# eBox_3G_SIM.net
KiCad netlist of a schematic drawn in Altium Designer
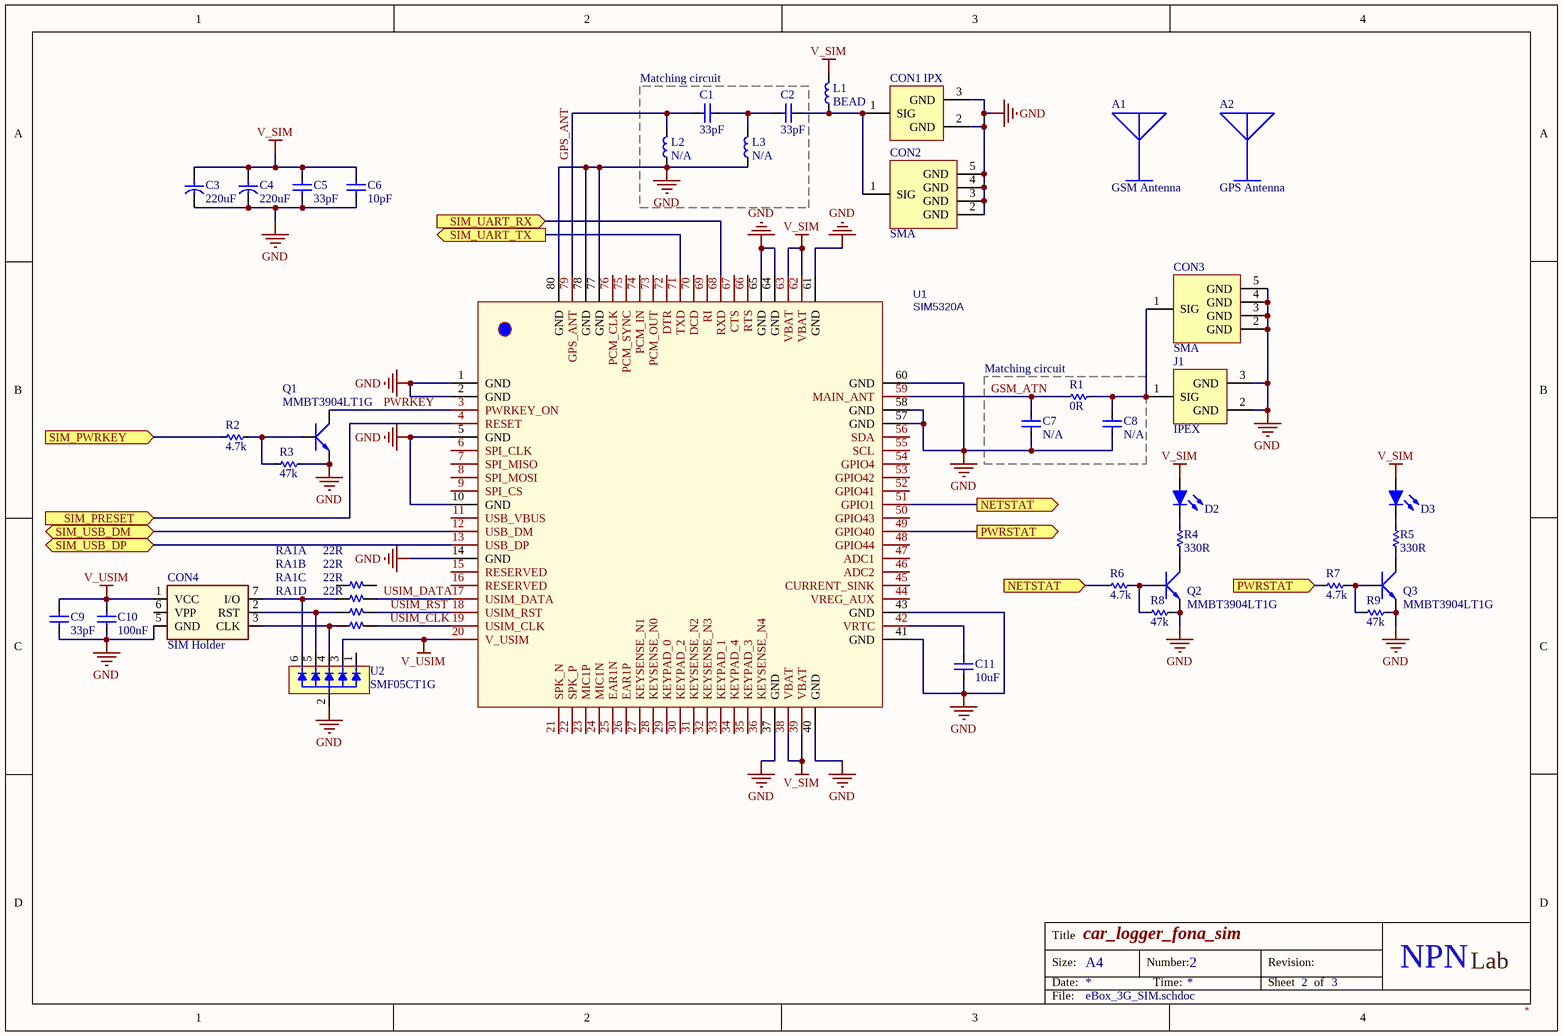
[diagram p0: eBox_3G_SIM.schdoc]

(export (version "E")
  (design (tool "Eeschema 10.0.6"))
  (components
    (comp (ref "A1")
      (value "GSM Antenna")
      (footprint "Antenna")
      (description "Antenna")
      (libsource (lib "car_logger_libs") (part "Antenna"))
    )
    (comp (ref "A2")
      (value "GPS Antenna")
      (footprint "Antenna")
      (description "Antenna")
      (libsource (lib "car_logger_libs") (part "Antenna"))
    )
    (comp (ref "C1")
      (value "33pF")
      (footprint "CC 0603")
      (description "CAP CER 33PF 100V C0G/NP0 0603")
      (fields
        (field (name "MANUFACTURER") "Murata Electronics")
        (field (name "MANUFACTURER PART NUMBER") "GCM1885C2A330JA16D")
      )
      (libsource (lib "car_logger_libs") (part "Capacitor NP"))
    )
    (comp (ref "C2")
      (value "33pF")
      (footprint "CC 0603")
      (description "CAP CER 33PF 100V C0G/NP0 0603")
      (fields
        (field (name "MANUFACTURER") "Murata Electronics")
        (field (name "MANUFACTURER PART NUMBER") "GCM1885C2A330JA16D")
      )
      (libsource (lib "car_logger_libs") (part "Capacitor NP"))
    )
    (comp (ref "C3")
      (value "220uF")
      (footprint "C SMD ALU (D8)")
      (description "CAP TANT POLY 100UF 6.3V 1210")
      (fields
        (field (name "MANUFACTURER") "AVX Corporation")
        (field (name "MANUFACTURER PART NUMBER") "TCJB107M006R0055")
      )
      (libsource (lib "ChipFC_Lib") (part "Capacitor"))
    )
    (comp (ref "C4")
      (value "220uF")
      (footprint "C SMD ALU (D8)")
      (description "CAP TANT POLY 100UF 6.3V 1210")
      (fields
        (field (name "MANUFACTURER") "AVX Corporation")
        (field (name "MANUFACTURER PART NUMBER") "TCJB107M006R0055")
      )
      (libsource (lib "ChipFC_Lib") (part "Capacitor"))
    )
    (comp (ref "C5")
      (value "33pF")
      (footprint "CC 0603")
      (description "CAP CER 33PF 100V C0G/NP0 0603")
      (fields
        (field (name "MANUFACTURER") "Murata Electronics")
        (field (name "MANUFACTURER PART NUMBER") "GCM1885C2A330JA16D")
      )
      (libsource (lib "car_logger_libs") (part "Capacitor NP"))
    )
    (comp (ref "C6")
      (value "10pF")
      (footprint "CC 0603")
      (description "CAP CER 10PF 100V C0G/NP0 0603")
      (fields
        (field (name "MANUFACTURER") "Murata Electronics")
        (field (name "MANUFACTURER PART NUMBER") "GCM1885C2A100JA16D")
      )
      (libsource (lib "car_logger_libs") (part "Capacitor NP"))
    )
    (comp (ref "C7")
      (value "N/A")
      (footprint "CC 0603")
      (description "CAP N/A")
      (libsource (lib "car_logger_libs") (part "Capacitor NP"))
    )
    (comp (ref "C8")
      (value "N/A")
      (footprint "CC 0603")
      (description "CAP N/A")
      (libsource (lib "car_logger_libs") (part "Capacitor NP"))
    )
    (comp (ref "C9")
      (value "33pF")
      (footprint "CC 0603")
      (description "CAP CER 33PF 100V C0G/NP0 0603")
      (fields
        (field (name "MANUFACTURER") "Murata Electronics")
        (field (name "MANUFACTURER PART NUMBER") "GCM1885C2A330JA16D")
      )
      (libsource (lib "car_logger_libs") (part "Capacitor NP"))
    )
    (comp (ref "C10")
      (value "100nF")
      (footprint "CC 0603")
      (description "CAP CER 0.1UF 16V X7R 0603")
      (fields
        (field (name "MANUFACTURER") "Murata Electronics")
        (field (name "MANUFACTURER PART NUMBER") "GCJ188R71C104KA01D")
      )
      (libsource (lib "car_logger_libs") (part "Capacitor NP"))
    )
    (comp (ref "C11")
      (value "10uF")
      (footprint "CC 0805")
      (description "CAP CER 10UF 10V X5R 0603")
      (fields
        (field (name "MANUFACTURER") "Murata Electronics")
        (field (name "MANUFACTURER PART NUMBER") "GRM188R61A106KE69D")
      )
      (libsource (lib "car_logger_libs") (part "Capacitor NP"))
    )
    (comp (ref "CON1")
      (value "IPX")
      (footprint "CONN/IPX/SMD")
      (libsource (lib "chipfc_altium_libs") (part "CON IPX"))
    )
    (comp (ref "CON2")
      (value "SMA")
      (footprint "CONN/SMA/RA")
      (description "SMA connectors")
      (libsource (lib "chipfc_altium_libs") (part "CON SMA"))
    )
    (comp (ref "CON3")
      (value "SMA")
      (footprint "CONN/SMA/RA")
      (description "SMA connectors")
      (libsource (lib "chipfc_altium_libs") (part "CON SMA"))
    )
    (comp (ref "CON4")
      (value "SIM Holder")
      (footprint "CON SIM Holder C707")
      (description "SIM Card holder, 6 pins")
      (libsource (lib "chipfc_altium_libs") (part "SIM holder 6 pin"))
    )
    (comp (ref "D2")
      (value "LED GREEN")
      (footprint "Led 0603 - green")
      (description "LED GREEN DIFFUSED 0603 SMD")
      (fields
        (field (name "MANUFACTURER") "Rohm Semiconductor")
        (field (name "MANUFACTURER PART NUMBER") "SML-D12P8WT86")
      )
      (libsource (lib "ChipFC_Lib") (part "Led"))
    )
    (comp (ref "D3")
      (value "LED RED")
      (footprint "Led 0603 - red")
      (description "LED RED DIFFUSED 0603 SMD")
      (fields
        (field (name "MANUFACTURER") "Rohm Semiconductor")
        (field (name "MANUFACTURER PART NUMBER") "SML-D12U8WT86")
      )
      (libsource (lib "ChipFC_Lib") (part "Led"))
    )
    (comp (ref "J1")
      (value "IPEX")
      (footprint "CONN/IPX/SMD")
      (description "CONN UMC RCPT STR 50 OHM SMD")
      (fields
        (field (name "MANUFACTURER") "Taoglas Limited")
        (field (name "MANUFACTURER PART NUMBER") "RECE.20279.001E.01")
      )
      (libsource (lib "ChipFC_Lib") (part "CON IPX"))
    )
    (comp (ref "L1")
      (value "BEAD")
      (footprint "LL 0603")
      (description "FERRITE BEAD 30 OHM 0603 1LN")
      (fields
        (field (name "MANUFACTURER") "Vishay Dale")
        (field (name "MANUFACTURER PART NUMBER") "ILBB0603ER300V")
      )
      (libsource (lib "car_logger_libs") (part "Inductor"))
    )
    (comp (ref "L2")
      (value "N/A")
      (footprint "LL 0603")
      (description "IND N/A")
      (libsource (lib "car_logger_libs") (part "Inductor"))
    )
    (comp (ref "L3")
      (value "N/A")
      (footprint "LL 0603")
      (description "IND N/A")
      (libsource (lib "car_logger_libs") (part "Inductor"))
    )
    (comp (ref "Q1")
      (value "MMBT3904LT1G")
      (footprint "SOT-23")
      (description "TRANS NPN 40V 0.2A SOT23")
      (fields (field (name "MANUFACTURER") "ON Semiconductor"))
      (libsource (lib "car_logger_libs") (part "MMBT3904LT1G"))
    )
    (comp (ref "Q2")
      (value "MMBT3904LT1G")
      (footprint "SOT-23")
      (description "TRANS NPN 40V 0.2A SOT23")
      (fields (field (name "MANUFACTURER") "ON Semiconductor"))
      (libsource (lib "car_logger_libs") (part "MMBT3904LT1G"))
    )
    (comp (ref "Q3")
      (value "MMBT3904LT1G")
      (footprint "SOT-23")
      (description "TRANS NPN 40V 0.2A SOT23")
      (fields (field (name "MANUFACTURER") "ON Semiconductor"))
      (libsource (lib "car_logger_libs") (part "MMBT3904LT1G"))
    )
    (comp (ref "R1")
      (value "0R")
      (footprint "RR 0603")
      (description "RES SMD 0 OHM JUMPER 1/10W 0603")
      (fields
        (field (name "MANUFACTURER") "Panasonic Industrial Devices")
        (field (name "MANUFACTURER PART NUMBER") "ERJ-3GEY0R00V")
      )
      (libsource (lib "car_logger_libs") (part "Resistors"))
    )
    (comp (ref "R2")
      (value "4.7k")
      (footprint "RR 0603")
      (description "RES SMD 4.7K OHM 1% 1/10W 0603")
      (fields
        (field (name "MANUFACTURER") "Panasonic Industrial Devices")
        (field (name "MANUFACTURER PART NUMBER") "ERJ-3EKF4701V")
      )
      (libsource (lib "car_logger_libs") (part "Resistors"))
    )
    (comp (ref "R3")
      (value "47k")
      (footprint "RR 0603")
      (description "RES SMD 47K OHM 5% 1/10W 0603")
      (fields
        (field (name "MANUFACTURER") "Panasonic Industrial Devices")
        (field (name "MANUFACTURER PART NUMBER") "ERJ-3GEYJ473V")
      )
      (libsource (lib "car_logger_libs") (part "Resistors"))
    )
    (comp (ref "R4")
      (value "330R")
      (footprint "RR 0603")
      (description "RES SMD 330 OHM 5% 1/10W 0603")
      (fields
        (field (name "MANUFACTURER") "Panasonic Industrial Devices")
        (field (name "MANUFACTURER PART NUMBER") "ERJ-3GEYJ331V")
      )
      (libsource (lib "car_logger_libs") (part "Resistors"))
    )
    (comp (ref "R5")
      (value "330R")
      (footprint "RR 0603")
      (description "RES SMD 330 OHM 5% 1/10W 0603")
      (fields
        (field (name "MANUFACTURER") "Panasonic Industrial Devices")
        (field (name "MANUFACTURER PART NUMBER") "ERJ-3GEYJ331V")
      )
      (libsource (lib "car_logger_libs") (part "Resistors"))
    )
    (comp (ref "R6")
      (value "4.7k")
      (footprint "RR 0603")
      (description "RES SMD 4.7K OHM 1% 1/10W 0603")
      (fields
        (field (name "MANUFACTURER") "Panasonic Industrial Devices")
        (field (name "MANUFACTURER PART NUMBER") "ERJ-3EKF4701V")
      )
      (libsource (lib "car_logger_libs") (part "Resistors"))
    )
    (comp (ref "R7")
      (value "4.7k")
      (footprint "RR 0603")
      (description "RES SMD 4.7K OHM 1% 1/10W 0603")
      (fields
        (field (name "MANUFACTURER") "Panasonic Industrial Devices")
        (field (name "MANUFACTURER PART NUMBER") "ERJ-3EKF4701V")
      )
      (libsource (lib "car_logger_libs") (part "Resistors"))
    )
    (comp (ref "R8")
      (value "47k")
      (footprint "RR 0603")
      (description "RES SMD 47K OHM 5% 1/10W 0603")
      (fields
        (field (name "MANUFACTURER") "Panasonic Industrial Devices")
        (field (name "MANUFACTURER PART NUMBER") "ERJ-3GEYJ473V")
      )
      (libsource (lib "car_logger_libs") (part "Resistors"))
    )
    (comp (ref "R9")
      (value "47k")
      (footprint "RR 0603")
      (description "RES SMD 47K OHM 5% 1/10W 0603")
      (fields
        (field (name "MANUFACTURER") "Panasonic Industrial Devices")
        (field (name "MANUFACTURER PART NUMBER") "ERJ-3GEYJ473V")
      )
      (libsource (lib "car_logger_libs") (part "Resistors"))
    )
    (comp (ref "RA1")
      (value "22R")
      (footprint "RAx4 1206 (3216)")
      (libsource (lib "chipfc_altium_libs") (part "Resistor Array x4"))
    )
    (comp (ref "U1")
      (value "SIM5320A")
      (footprint "SIM5320")
      (libsource (lib "car_logger_libs") (part "SIM5320A"))
    )
    (comp (ref "U2")
      (value "SMF05CT1G")
      (footprint "SOT-363-6")
      (description "TVS DIODE 5V 12.5V SC88")
      (fields (field (name "MANUFACTURER") "ON Semiconductor"))
      (libsource (lib "car_logger_libs") (part "SMF05C"))
    )
  )
  (nets
    (net (code "1") (name "/GPS_ANT") (class "Default")
      (node (ref "C1") (pin "2") (pinfunction "2_2") (pintype "passive"))
      (node (ref "L2") (pin "2") (pinfunction "2_2") (pintype "passive"))
      (node (ref "U1") (pin "79") (pinfunction "GPS_ANT_79") (pintype "passive"))
    )
    (net (code "2") (name "/GSM_ATN") (class "Default")
      (node (ref "C7") (pin "2") (pinfunction "2_2") (pintype "passive"))
      (node (ref "R1") (pin "2") (pinfunction "2_2") (pintype "passive"))
      (node (ref "U1") (pin "59") (pinfunction "MAIN_ANT_59") (pintype "passive"))
    )
    (net (code "3") (name "/NETSTAT") (class "Default")
      (node (ref "R6") (pin "1") (pinfunction "1_1") (pintype "passive"))
      (node (ref "U1") (pin "51") (pinfunction "GPIO1_51") (pintype "passive"))
    )
    (net (code "4") (name "/PWRKEY") (class "Default")
      (node (ref "Q1") (pin "3") (pinfunction "C_3") (pintype "passive"))
      (node (ref "U1") (pin "3") (pinfunction "PWRKEY_ON_3") (pintype "passive"))
    )
    (net (code "5") (name "/PWRSTAT") (class "Default")
      (node (ref "R7") (pin "1") (pinfunction "1_1") (pintype "passive"))
      (node (ref "U1") (pin "49") (pinfunction "GPIO40_49") (pintype "passive"))
    )
    (net (code "6") (name "/SIM_PRESET") (class "Default")
      (node (ref "U1") (pin "4") (pinfunction "RESET_4") (pintype "passive"))
    )
    (net (code "7") (name "/SIM_PWRKEY") (class "Default")
      (node (ref "R2") (pin "1") (pinfunction "1_1") (pintype "passive"))
    )
    (net (code "8") (name "/SIM_UART_RX") (class "Default")
      (node (ref "U1") (pin "68") (pinfunction "RXD_68") (pintype "passive"))
    )
    (net (code "9") (name "/SIM_UART_TX") (class "Default")
      (node (ref "U1") (pin "71") (pinfunction "TXD_71") (pintype "passive"))
    )
    (net (code "10") (name "/SIM_USB_DM") (class "Default")
      (node (ref "U1") (pin "12") (pinfunction "USB_DM_12") (pintype "passive"))
    )
    (net (code "11") (name "/SIM_USB_DP") (class "Default")
      (node (ref "U1") (pin "13") (pinfunction "USB_DP_13") (pintype "passive"))
    )
    (net (code "12") (name "/USIM_CLK") (class "Default")
      (node (ref "RA1") (pin "5") (pinfunction "5_5") (pintype "passive"))
      (node (ref "U1") (pin "19") (pinfunction "USIM_CLK_19") (pintype "passive"))
    )
    (net (code "13") (name "/USIM_DATA") (class "Default")
      (node (ref "RA1") (pin "7") (pinfunction "7_7") (pintype "passive"))
      (node (ref "U1") (pin "17") (pinfunction "USIM_DATA_17") (pintype "passive"))
    )
    (net (code "14") (name "/USIM_RST") (class "Default")
      (node (ref "RA1") (pin "6") (pinfunction "6_6") (pintype "passive"))
      (node (ref "U1") (pin "18") (pinfunction "USIM_RST_18") (pintype "passive"))
    )
    (net (code "15") (name "GND") (class "Default")
      (node (ref "C10") (pin "2") (pinfunction "2_2") (pintype "passive"))
      (node (ref "C11") (pin "1") (pinfunction "1_1") (pintype "passive"))
      (node (ref "C3") (pin "2") (pinfunction "2_2") (pintype "passive"))
      (node (ref "C4") (pin "2") (pinfunction "2_2") (pintype "passive"))
      (node (ref "C5") (pin "1") (pinfunction "1_1") (pintype "passive"))
      (node (ref "C6") (pin "1") (pinfunction "1_1") (pintype "passive"))
      (node (ref "C7") (pin "1") (pinfunction "1_1") (pintype "passive"))
      (node (ref "C8") (pin "1") (pinfunction "1_1") (pintype "passive"))
      (node (ref "C9") (pin "2") (pinfunction "2_2") (pintype "passive"))
      (node (ref "CON1") (pin "2") (pinfunction "GND_2") (pintype "passive"))
      (node (ref "CON1") (pin "3") (pinfunction "GND_3") (pintype "passive"))
      (node (ref "CON2") (pin "2") (pinfunction "GND_2") (pintype "passive"))
      (node (ref "CON2") (pin "3") (pinfunction "GND_3") (pintype "passive"))
      (node (ref "CON2") (pin "4") (pinfunction "GND_4") (pintype "passive"))
      (node (ref "CON2") (pin "5") (pinfunction "GND_5") (pintype "passive"))
      (node (ref "CON3") (pin "2") (pinfunction "GND_2") (pintype "passive"))
      (node (ref "CON3") (pin "3") (pinfunction "GND_3") (pintype "passive"))
      (node (ref "CON3") (pin "4") (pinfunction "GND_4") (pintype "passive"))
      (node (ref "CON3") (pin "5") (pinfunction "GND_5") (pintype "passive"))
      (node (ref "CON4") (pin "5") (pinfunction "GND_5") (pintype "power_in"))
      (node (ref "J1") (pin "2") (pinfunction "GND_2") (pintype "passive"))
      (node (ref "J1") (pin "3") (pinfunction "GND_3") (pintype "passive"))
      (node (ref "L2") (pin "1") (pinfunction "1_1") (pintype "passive"))
      (node (ref "L3") (pin "1") (pinfunction "1_1") (pintype "passive"))
      (node (ref "Q1") (pin "2") (pinfunction "E_2") (pintype "passive"))
      (node (ref "Q2") (pin "2") (pinfunction "E_2") (pintype "passive"))
      (node (ref "Q3") (pin "2") (pinfunction "E_2") (pintype "passive"))
      (node (ref "R3") (pin "2") (pinfunction "2_2") (pintype "passive"))
      (node (ref "R8") (pin "2") (pinfunction "2_2") (pintype "passive"))
      (node (ref "R9") (pin "2") (pinfunction "2_2") (pintype "passive"))
      (node (ref "U1") (pin "1") (pinfunction "GND_1") (pintype "passive"))
      (node (ref "U1") (pin "10") (pinfunction "GND_10") (pintype "passive"))
      (node (ref "U1") (pin "14") (pinfunction "GND_14") (pintype "passive"))
      (node (ref "U1") (pin "2") (pinfunction "GND_2") (pintype "passive"))
      (node (ref "U1") (pin "37") (pinfunction "GND_37") (pintype "passive"))
      (node (ref "U1") (pin "40") (pinfunction "GND_40") (pintype "passive"))
      (node (ref "U1") (pin "41") (pinfunction "GND_41") (pintype "passive"))
      (node (ref "U1") (pin "43") (pinfunction "GND_43") (pintype "passive"))
      (node (ref "U1") (pin "5") (pinfunction "GND_5") (pintype "passive"))
      (node (ref "U1") (pin "57") (pinfunction "GND_57") (pintype "passive"))
      (node (ref "U1") (pin "58") (pinfunction "GND_58") (pintype "passive"))
      (node (ref "U1") (pin "60") (pinfunction "GND_60") (pintype "passive"))
      (node (ref "U1") (pin "61") (pinfunction "GND_61") (pintype "passive"))
      (node (ref "U1") (pin "64") (pinfunction "GND_64") (pintype "passive"))
      (node (ref "U1") (pin "65") (pinfunction "GND_65") (pintype "passive"))
      (node (ref "U1") (pin "77") (pinfunction "GND_77") (pintype "passive"))
      (node (ref "U1") (pin "78") (pinfunction "GND_78") (pintype "passive"))
      (node (ref "U1") (pin "80") (pinfunction "GND_80") (pintype "passive"))
      (node (ref "U2") (pin "2") (pinfunction "A_2") (pintype "passive"))
    )
    (net (code "16") (name "Net-(C1-Pad1)") (class "Default")
      (node (ref "C1") (pin "1") (pinfunction "1_1") (pintype "passive"))
      (node (ref "C2") (pin "2") (pinfunction "2_2") (pintype "passive"))
      (node (ref "L3") (pin "2") (pinfunction "2_2") (pintype "passive"))
    )
    (net (code "17") (name "Net-(CON1-SIG)") (class "Default")
      (node (ref "C2") (pin "1") (pinfunction "1_1") (pintype "passive"))
      (node (ref "CON1") (pin "1") (pinfunction "SIG_1") (pintype "passive"))
      (node (ref "CON2") (pin "1") (pinfunction "SIG_1") (pintype "passive"))
      (node (ref "L1") (pin "1") (pinfunction "1_1") (pintype "passive"))
    )
    (net (code "18") (name "Net-(CON3-SIG)") (class "Default")
      (node (ref "C8") (pin "2") (pinfunction "2_2") (pintype "passive"))
      (node (ref "CON3") (pin "1") (pinfunction "SIG_1") (pintype "passive"))
      (node (ref "J1") (pin "1") (pinfunction "SIG_1") (pintype "passive"))
      (node (ref "R1") (pin "1") (pinfunction "1_1") (pintype "passive"))
    )
    (net (code "19") (name "Net-(CON4-CLK)") (class "Default")
      (node (ref "CON4") (pin "3") (pinfunction "CLK_3") (pintype "passive"))
      (node (ref "RA1") (pin "4") (pinfunction "4_4") (pintype "passive"))
      (node (ref "U2") (pin "4") (pinfunction "K4_4") (pintype "passive"))
    )
    (net (code "20") (name "Net-(CON4-I{slash}O)") (class "Default")
      (node (ref "CON4") (pin "7") (pinfunction "I/O_7") (pintype "passive"))
      (node (ref "RA1") (pin "2") (pinfunction "2_2") (pintype "passive"))
      (node (ref "U2") (pin "6") (pinfunction "K6_6") (pintype "passive"))
    )
    (net (code "21") (name "Net-(CON4-RST)") (class "Default")
      (node (ref "CON4") (pin "2") (pinfunction "RST_2") (pintype "passive"))
      (node (ref "RA1") (pin "3") (pinfunction "3_3") (pintype "passive"))
      (node (ref "U2") (pin "5") (pinfunction "K5_5") (pintype "passive"))
    )
    (net (code "22") (name "Net-(D2-K)") (class "Default")
      (node (ref "D2") (pin "2") (pinfunction "K_2") (pintype "passive"))
      (node (ref "R4") (pin "2") (pinfunction "2_2") (pintype "passive"))
    )
    (net (code "23") (name "Net-(D3-K)") (class "Default")
      (node (ref "D3") (pin "2") (pinfunction "K_2") (pintype "passive"))
      (node (ref "R5") (pin "2") (pinfunction "2_2") (pintype "passive"))
    )
    (net (code "24") (name "Net-(Q1-B)") (class "Default")
      (node (ref "Q1") (pin "1") (pinfunction "B_1") (pintype "passive"))
      (node (ref "R2") (pin "2") (pinfunction "2_2") (pintype "passive"))
      (node (ref "R3") (pin "1") (pinfunction "1_1") (pintype "passive"))
    )
    (net (code "25") (name "Net-(Q2-B)") (class "Default")
      (node (ref "Q2") (pin "1") (pinfunction "B_1") (pintype "passive"))
      (node (ref "R6") (pin "2") (pinfunction "2_2") (pintype "passive"))
      (node (ref "R8") (pin "1") (pinfunction "1_1") (pintype "passive"))
    )
    (net (code "26") (name "Net-(Q2-C)") (class "Default")
      (node (ref "Q2") (pin "3") (pinfunction "C_3") (pintype "passive"))
      (node (ref "R4") (pin "1") (pinfunction "1_1") (pintype "passive"))
    )
    (net (code "27") (name "Net-(Q3-B)") (class "Default")
      (node (ref "Q3") (pin "1") (pinfunction "B_1") (pintype "passive"))
      (node (ref "R7") (pin "2") (pinfunction "2_2") (pintype "passive"))
      (node (ref "R9") (pin "1") (pinfunction "1_1") (pintype "passive"))
    )
    (net (code "28") (name "Net-(Q3-C)") (class "Default")
      (node (ref "Q3") (pin "3") (pinfunction "C_3") (pintype "passive"))
      (node (ref "R5") (pin "1") (pinfunction "1_1") (pintype "passive"))
    )
    (net (code "29") (name "Net-(U1-VRTC)") (class "Default")
      (node (ref "C11") (pin "2") (pinfunction "2_2") (pintype "passive"))
      (node (ref "U1") (pin "42") (pinfunction "VRTC_42") (pintype "passive"))
    )
    (net (code "30") (name "V_SIM") (class "Default")
      (node (ref "C3") (pin "1") (pinfunction "1_1") (pintype "passive"))
      (node (ref "C4") (pin "1") (pinfunction "1_1") (pintype "passive"))
      (node (ref "C5") (pin "2") (pinfunction "2_2") (pintype "passive"))
      (node (ref "C6") (pin "2") (pinfunction "2_2") (pintype "passive"))
      (node (ref "D2") (pin "1") (pinfunction "A_1") (pintype "passive"))
      (node (ref "D3") (pin "1") (pinfunction "A_1") (pintype "passive"))
      (node (ref "L1") (pin "2") (pinfunction "2_2") (pintype "passive"))
      (node (ref "U1") (pin "38") (pinfunction "VBAT_38") (pintype "passive"))
      (node (ref "U1") (pin "39") (pinfunction "VBAT_39") (pintype "passive"))
      (node (ref "U1") (pin "62") (pinfunction "VBAT_62") (pintype "passive"))
      (node (ref "U1") (pin "63") (pinfunction "VBAT_63") (pintype "passive"))
    )
    (net (code "31") (name "V_USIM") (class "Default")
      (node (ref "C10") (pin "1") (pinfunction "1_1") (pintype "passive"))
      (node (ref "C9") (pin "1") (pinfunction "1_1") (pintype "passive"))
      (node (ref "CON4") (pin "1") (pinfunction "VCC_1") (pintype "power_in"))
      (node (ref "U1") (pin "20") (pinfunction "V_USIM_20") (pintype "passive"))
      (node (ref "U2") (pin "3") (pinfunction "K3_3") (pintype "passive"))
    )
    (net (code "32") (name "unconnected-(CON4-VPP-Pad6)") (class "Default")
      (node (ref "CON4") (pin "6") (pinfunction "VPP_6") (pintype "passive"))
    )
    (net (code "33") (name "unconnected-(RA1-Pad1)") (class "Default")
      (node (ref "RA1") (pin "1") (pinfunction "1_1") (pintype "passive"))
    )
    (net (code "34") (name "unconnected-(RA1-Pad8)") (class "Default")
      (node (ref "RA1") (pin "8") (pinfunction "8_8") (pintype "passive"))
    )
    (net (code "35") (name "unconnected-(U1-ADC1-Pad47)") (class "Default")
      (node (ref "U1") (pin "47") (pinfunction "ADC1_47") (pintype "passive"))
    )
    (net (code "36") (name "unconnected-(U1-ADC2-Pad46)") (class "Default")
      (node (ref "U1") (pin "46") (pinfunction "ADC2_46") (pintype "passive"))
    )
    (net (code "37") (name "unconnected-(U1-CTS-Pad67)") (class "Default")
      (node (ref "U1") (pin "67") (pinfunction "CTS_67") (pintype "passive"))
    )
    (net (code "38") (name "unconnected-(U1-CURRENT_SINK-Pad45)") (class "Default")
      (node (ref "U1") (pin "45") (pinfunction "CURRENT_SINK_45") (pintype "passive"))
    )
    (net (code "39") (name "unconnected-(U1-DCD-Pad70)") (class "Default")
      (node (ref "U1") (pin "70") (pinfunction "DCD_70") (pintype "passive"))
    )
    (net (code "40") (name "unconnected-(U1-DTR-Pad72)") (class "Default")
      (node (ref "U1") (pin "72") (pinfunction "DTR_72") (pintype "passive"))
    )
    (net (code "41") (name "unconnected-(U1-EAR1N-Pad25)") (class "Default")
      (node (ref "U1") (pin "25") (pinfunction "EAR1N_25") (pintype "passive"))
    )
    (net (code "42") (name "unconnected-(U1-EAR1P-Pad26)") (class "Default")
      (node (ref "U1") (pin "26") (pinfunction "EAR1P_26") (pintype "passive"))
    )
    (net (code "43") (name "unconnected-(U1-GPIO4-Pad54)") (class "Default")
      (node (ref "U1") (pin "54") (pinfunction "GPIO4_54") (pintype "passive"))
    )
    (net (code "44") (name "unconnected-(U1-GPIO41-Pad52)") (class "Default")
      (node (ref "U1") (pin "52") (pinfunction "GPIO41_52") (pintype "passive"))
    )
    (net (code "45") (name "unconnected-(U1-GPIO42-Pad53)") (class "Default")
      (node (ref "U1") (pin "53") (pinfunction "GPIO42_53") (pintype "passive"))
    )
    (net (code "46") (name "unconnected-(U1-GPIO43-Pad50)") (class "Default")
      (node (ref "U1") (pin "50") (pinfunction "GPIO43_50") (pintype "passive"))
    )
    (net (code "47") (name "unconnected-(U1-GPIO44-Pad48)") (class "Default")
      (node (ref "U1") (pin "48") (pinfunction "GPIO44_48") (pintype "passive"))
    )
    (net (code "48") (name "unconnected-(U1-KEYPAD_0-Pad29)") (class "Default")
      (node (ref "U1") (pin "29") (pinfunction "KEYPAD_0_29") (pintype "passive"))
    )
    (net (code "49") (name "unconnected-(U1-KEYPAD_1-Pad33)") (class "Default")
      (node (ref "U1") (pin "33") (pinfunction "KEYPAD_1_33") (pintype "passive"))
    )
    (net (code "50") (name "unconnected-(U1-KEYPAD_2-Pad30)") (class "Default")
      (node (ref "U1") (pin "30") (pinfunction "KEYPAD_2_30") (pintype "passive"))
    )
    (net (code "51") (name "unconnected-(U1-KEYPAD_3-Pad35)") (class "Default")
      (node (ref "U1") (pin "35") (pinfunction "KEYPAD_3_35") (pintype "passive"))
    )
    (net (code "52") (name "unconnected-(U1-KEYPAD_4-Pad34)") (class "Default")
      (node (ref "U1") (pin "34") (pinfunction "KEYPAD_4_34") (pintype "passive"))
    )
    (net (code "53") (name "unconnected-(U1-KEYSENSE_N0-Pad28)") (class "Default")
      (node (ref "U1") (pin "28") (pinfunction "KEYSENSE_N0_28") (pintype "passive"))
    )
    (net (code "54") (name "unconnected-(U1-KEYSENSE_N1-Pad27)") (class "Default")
      (node (ref "U1") (pin "27") (pinfunction "KEYSENSE_N1_27") (pintype "passive"))
    )
    (net (code "55") (name "unconnected-(U1-KEYSENSE_N2-Pad31)") (class "Default")
      (node (ref "U1") (pin "31") (pinfunction "KEYSENSE_N2_31") (pintype "passive"))
    )
    (net (code "56") (name "unconnected-(U1-KEYSENSE_N3-Pad32)") (class "Default")
      (node (ref "U1") (pin "32") (pinfunction "KEYSENSE_N3_32") (pintype "passive"))
    )
    (net (code "57") (name "unconnected-(U1-KEYSENSE_N4-Pad36)") (class "Default")
      (node (ref "U1") (pin "36") (pinfunction "KEYSENSE_N4_36") (pintype "passive"))
    )
    (net (code "58") (name "unconnected-(U1-MIC1N-Pad24)") (class "Default")
      (node (ref "U1") (pin "24") (pinfunction "MIC1N_24") (pintype "passive"))
    )
    (net (code "59") (name "unconnected-(U1-MIC1P-Pad23)") (class "Default")
      (node (ref "U1") (pin "23") (pinfunction "MIC1P_23") (pintype "passive"))
    )
    (net (code "60") (name "unconnected-(U1-PCM_CLK-Pad76)") (class "Default")
      (node (ref "U1") (pin "76") (pinfunction "PCM_CLK_76") (pintype "passive"))
    )
    (net (code "61") (name "unconnected-(U1-PCM_IN-Pad74)") (class "Default")
      (node (ref "U1") (pin "74") (pinfunction "PCM_IN_74") (pintype "passive"))
    )
    (net (code "62") (name "unconnected-(U1-PCM_OUT-Pad73)") (class "Default")
      (node (ref "U1") (pin "73") (pinfunction "PCM_OUT_73") (pintype "passive"))
    )
    (net (code "63") (name "unconnected-(U1-PCM_SYNC-Pad75)") (class "Default")
      (node (ref "U1") (pin "75") (pinfunction "PCM_SYNC_75") (pintype "passive"))
    )
    (net (code "64") (name "unconnected-(U1-RESERVED-Pad15)") (class "Default")
      (node (ref "U1") (pin "15") (pinfunction "RESERVED_15") (pintype "passive"))
    )
    (net (code "65") (name "unconnected-(U1-RESERVED-Pad16)") (class "Default")
      (node (ref "U1") (pin "16") (pinfunction "RESERVED_16") (pintype "passive"))
    )
    (net (code "66") (name "unconnected-(U1-RI-Pad69)") (class "Default")
      (node (ref "U1") (pin "69") (pinfunction "RI_69") (pintype "passive"))
    )
    (net (code "67") (name "unconnected-(U1-RTS-Pad66)") (class "Default")
      (node (ref "U1") (pin "66") (pinfunction "RTS_66") (pintype "passive"))
    )
    (net (code "68") (name "unconnected-(U1-SCL-Pad55)") (class "Default")
      (node (ref "U1") (pin "55") (pinfunction "SCL_55") (pintype "passive"))
    )
    (net (code "69") (name "unconnected-(U1-SDA-Pad56)") (class "Default")
      (node (ref "U1") (pin "56") (pinfunction "SDA_56") (pintype "passive"))
    )
    (net (code "70") (name "unconnected-(U1-SPI_CLK-Pad6)") (class "Default")
      (node (ref "U1") (pin "6") (pinfunction "SPI_CLK_6") (pintype "passive"))
    )
    (net (code "71") (name "unconnected-(U1-SPI_CS-Pad9)") (class "Default")
      (node (ref "U1") (pin "9") (pinfunction "SPI_CS_9") (pintype "passive"))
    )
    (net (code "72") (name "unconnected-(U1-SPI_MISO-Pad7)") (class "Default")
      (node (ref "U1") (pin "7") (pinfunction "SPI_MISO_7") (pintype "passive"))
    )
    (net (code "73") (name "unconnected-(U1-SPI_MOSI-Pad8)") (class "Default")
      (node (ref "U1") (pin "8") (pinfunction "SPI_MOSI_8") (pintype "passive"))
    )
    (net (code "74") (name "unconnected-(U1-SPK_N-Pad21)") (class "Default")
      (node (ref "U1") (pin "21") (pinfunction "SPK_N_21") (pintype "passive"))
    )
    (net (code "75") (name "unconnected-(U1-SPK_P-Pad22)") (class "Default")
      (node (ref "U1") (pin "22") (pinfunction "SPK_P_22") (pintype "passive"))
    )
    (net (code "76") (name "unconnected-(U1-USB_VBUS-Pad11)") (class "Default")
      (node (ref "U1") (pin "11") (pinfunction "USB_VBUS_11") (pintype "passive"))
    )
    (net (code "77") (name "unconnected-(U1-VREG_AUX-Pad44)") (class "Default")
      (node (ref "U1") (pin "44") (pinfunction "VREG_AUX_44") (pintype "passive"))
    )
    (net (code "78") (name "unconnected-(U2-K1-Pad1)") (class "Default")
      (node (ref "U2") (pin "1") (pinfunction "K1_1") (pintype "passive"))
    )
  )
)
